# 07_EEPR_DISCHAR.net
KiCad netlist of a schematic drawn in Altium Designer
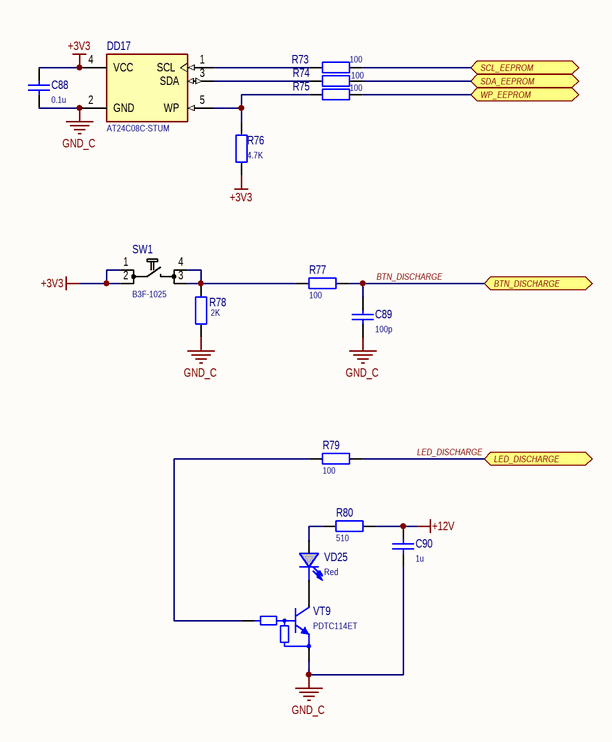
[diagram p0: 07_EEPR_DISCHAR.SchDoc]

(export (version "E")
  (design (tool "Eeschema 10.0.6"))
  (components
    (comp (ref "C88")
      (value "0.1u")
      (footprint "mainLib:SMD_C_0603")
      (description "SMD C 0603 MURATA 50V 10% X7R")
      (fields (field (name "PARTNUMBER") "GRM188R71H104K") (field (name "MANUFACTURER") "MURATA"))
      (libsource (lib "mainRCLib") (part "C0603 0.1u 50V 10%"))
    )
    (comp (ref "C89")
      (value "100p")
      (footprint "mainLib:SMD_C_0603")
      (description "SMD C 0603 MURATA 100V 5% NP0")
      (fields (field (name "PARTNUMBER") "GRM1885C2A101JA01") (field (name "MANUFACTURER") "MURATA"))
      (libsource (lib "mainRCLib") (part "C0603 100p 100V 5%"))
    )
    (comp (ref "C90")
      (value "1u")
      (footprint "mainLib:SMD_C_0603")
      (description "SMD C 0603 MURATA 25V 10% X7R")
      (fields (field (name "PARTNUMBER") "GRM188R71E105KA12") (field (name "MANUFACTURER") "MURATA"))
      (libsource (lib "mainRCLib") (part "C0603 1uF 25V 10%"))
    )
    (comp (ref "DD17")
      (value "AT24C08C-STUM")
      (footprint "mainLib:5TS1")
      (description "I2C Serial EEPROM, 8-Kbit (1024 x 8)")
      (fields (field (name "PARTNUMBER") "AT24C08C-STUM-T") (field (name "MANUFACTURER") "ATMEL"))
      (libsource (lib "mainLib") (part "AT24C08C-STUM"))
    )
    (comp (ref "R73")
      (value "100")
      (footprint "SMD_R_0603")
      (description "SMD R 0603 VISHAY 0.1W 75V 1% 100ppm")
      (fields (field (name "PARTNUMBER") "CRCW0603100RFK") (field (name "MANUFACTURER") "VISHAY"))
      (libsource (lib "mainRCLib") (part "R0603 100 1%"))
    )
    (comp (ref "R74")
      (value "100")
      (footprint "SMD_R_0603")
      (description "SMD R 0603 VISHAY 0.1W 75V 1% 100ppm")
      (fields (field (name "PARTNUMBER") "CRCW0603100RFK") (field (name "MANUFACTURER") "VISHAY"))
      (libsource (lib "mainRCLib") (part "R0603 100 1%"))
    )
    (comp (ref "R75")
      (value "100")
      (footprint "SMD_R_0603")
      (description "SMD R 0603 VISHAY 0.1W 75V 1% 100ppm")
      (fields (field (name "PARTNUMBER") "CRCW0603100RFK") (field (name "MANUFACTURER") "VISHAY"))
      (libsource (lib "mainRCLib") (part "R0603 100 1%"))
    )
    (comp (ref "R76")
      (value "4.7K")
      (footprint "mainLib:SMD_R_0805")
      (description "SMD R 0805 VISHAY 0.125W 150V 1% 100ppm")
      (fields (field (name "PARTNUMBER") "CRCW08054K70FK") (field (name "MANUFACTURER") "VISHAY"))
      (libsource (lib "mainRCLib") (part "R0805 4.7K 1%"))
    )
    (comp (ref "R77")
      (value "100")
      (footprint "SMD_R_0603")
      (description "SMD R 0603 VISHAY 0.1W 75V 1% 100ppm")
      (fields (field (name "PARTNUMBER") "CRCW0603100RFK") (field (name "MANUFACTURER") "VISHAY"))
      (libsource (lib "mainRCLib") (part "R0603 100 1%"))
    )
    (comp (ref "R78")
      (value "2K")
      (footprint "mainLib:SMD_R_0805")
      (description "SMD R 0805 VISHAY 0.125W 150V 1% 100ppm")
      (fields (field (name "PARTNUMBER") "CRCW08052K00FK") (field (name "MANUFACTURER") "VISHAY"))
      (libsource (lib "mainRCLib") (part "R0805 2K 1%"))
    )
    (comp (ref "R79")
      (value "100")
      (footprint "SMD_R_0603")
      (description "SMD R 0603 VISHAY 0.1W 75V 1% 100ppm")
      (fields (field (name "PARTNUMBER") "CRCW0603100RFK") (field (name "MANUFACTURER") "VISHAY"))
      (libsource (lib "mainRCLib") (part "R0603 100 1%"))
    )
    (comp (ref "R80")
      (value "510")
      (footprint "mainLib:SMD_R_1206")
      (description "SMD R 1206 VISHAY 0.25W 200V 1% 100ppm")
      (fields (field (name "PARTNUMBER") "CRCW1206510RFK") (field (name "MANUFACTURER") "VISHAY"))
      (libsource (lib "mainRCLib") (part "R1206 510 1%"))
    )
    (comp (ref "SW1")
      (value "B3F-1025")
      (footprint "mainLib:B3F-1025 (no gnd)")
      (description "1-50mA; 5-24V; 6x6mm h=5mm; Red")
      (fields (field (name "MANUFACTURER") "Omron"))
      (libsource (lib "mainLib") (part "B3F-1025"))
    )
    (comp (ref "VD25")
      (value "Red")
      (footprint "mainLib:SMD_LED_LL_Red")
      (description "LED Red SMD")
      (fields (field (name "PARTNUMBER") "LL-S172SC-2S") (field (name "MANUFACTURER") "Lucky Light"))
      (libsource (lib "mainLib") (part "LL-S172SC-2S"))
    )
    (comp (ref "VT9")
      (value "PDTC114ET")
      (footprint "mainLib:SOT23-3")
      (description "Digital Transistor (BRT), R1=10 kOhm, R2=10 kOhm, NPN Transistor")
      (fields (field (name "MANUFACTURER") "On Semiconductor"))
      (libsource (lib "mainLib") (part "PDTC114ET"))
    )
  )
  (nets
    (net (code "1") (name "+3V3") (class "Default")
      (node (ref "C88") (pin "2") (pinfunction "2_2") (pintype "passive"))
      (node (ref "DD17") (pin "4") (pinfunction "VCC_4") (pintype "power_in"))
      (node (ref "R76") (pin "1") (pinfunction "1_1") (pintype "passive"))
      (node (ref "SW1") (pin "1") (pinfunction "1_1") (pintype "passive"))
      (node (ref "SW1") (pin "2") (pinfunction "2_2") (pintype "passive"))
    )
    (net (code "2") (name "+12V") (class "Default")
      (node (ref "C90") (pin "2") (pinfunction "2_2") (pintype "passive"))
      (node (ref "R80") (pin "2") (pinfunction "2_2") (pintype "passive"))
    )
    (net (code "3") (name "/BTN_DISCHARGE") (class "Default")
      (node (ref "C89") (pin "2") (pinfunction "2_2") (pintype "passive"))
      (node (ref "R77") (pin "2") (pinfunction "2_2") (pintype "passive"))
    )
    (net (code "4") (name "/LED_DISCHARGE") (class "Default")
      (node (ref "R79") (pin "2") (pinfunction "2_2") (pintype "passive"))
    )
    (net (code "5") (name "/SCL_EEPROM") (class "Default")
      (node (ref "R73") (pin "2") (pinfunction "2_2") (pintype "passive"))
    )
    (net (code "6") (name "/SDA_EEPROM") (class "Default")
      (node (ref "R74") (pin "2") (pinfunction "2_2") (pintype "passive"))
    )
    (net (code "7") (name "/WP_EEPROM") (class "Default")
      (node (ref "R75") (pin "2") (pinfunction "2_2") (pintype "passive"))
    )
    (net (code "8") (name "GND_C") (class "Default")
      (node (ref "C88") (pin "1") (pinfunction "1_1") (pintype "passive"))
      (node (ref "C89") (pin "1") (pinfunction "1_1") (pintype "passive"))
      (node (ref "C90") (pin "1") (pinfunction "1_1") (pintype "passive"))
      (node (ref "DD17") (pin "2") (pinfunction "GND_2") (pintype "power_in"))
      (node (ref "R78") (pin "1") (pinfunction "1_1") (pintype "passive"))
      (node (ref "VT9") (pin "2") (pinfunction "E_2") (pintype "passive"))
    )
    (net (code "9") (name "Net-(DD17-SCL)") (class "Default")
      (node (ref "DD17") (pin "1") (pinfunction "SCL_1") (pintype "input"))
      (node (ref "R73") (pin "1") (pinfunction "1_1") (pintype "passive"))
    )
    (net (code "10") (name "Net-(DD17-SDA)") (class "Default")
      (node (ref "DD17") (pin "3") (pinfunction "SDA_3") (pintype "bidirectional"))
      (node (ref "R74") (pin "1") (pinfunction "1_1") (pintype "passive"))
    )
    (net (code "11") (name "Net-(DD17-WP)") (class "Default")
      (node (ref "DD17") (pin "5") (pinfunction "WP_5") (pintype "input"))
      (node (ref "R75") (pin "1") (pinfunction "1_1") (pintype "passive"))
      (node (ref "R76") (pin "2") (pinfunction "2_2") (pintype "passive"))
    )
    (net (code "12") (name "Net-(R77-Pad1)") (class "Default")
      (node (ref "R77") (pin "1") (pinfunction "1_1") (pintype "passive"))
      (node (ref "R78") (pin "2") (pinfunction "2_2") (pintype "passive"))
      (node (ref "SW1") (pin "3") (pinfunction "3_3") (pintype "passive"))
      (node (ref "SW1") (pin "4") (pinfunction "4_4") (pintype "passive"))
    )
    (net (code "13") (name "Net-(VD25-ANODE)") (class "Default")
      (node (ref "R80") (pin "1") (pinfunction "1_1") (pintype "passive"))
      (node (ref "VD25") (pin "1") (pinfunction "ANODE_1") (pintype "passive"))
    )
    (net (code "14") (name "Net-(VD25-CATHODE)") (class "Default")
      (node (ref "VD25") (pin "2") (pinfunction "CATHODE_2") (pintype "passive"))
      (node (ref "VT9") (pin "3") (pinfunction "C_3") (pintype "passive"))
    )
    (net (code "15") (name "Net-(VT9-B)") (class "Default")
      (node (ref "R79") (pin "1") (pinfunction "1_1") (pintype "passive"))
      (node (ref "VT9") (pin "1") (pinfunction "B_1") (pintype "passive"))
    )
  )
)
